# motor_connector_board.net
KiCad netlist of a schematic drawn in EAGLE
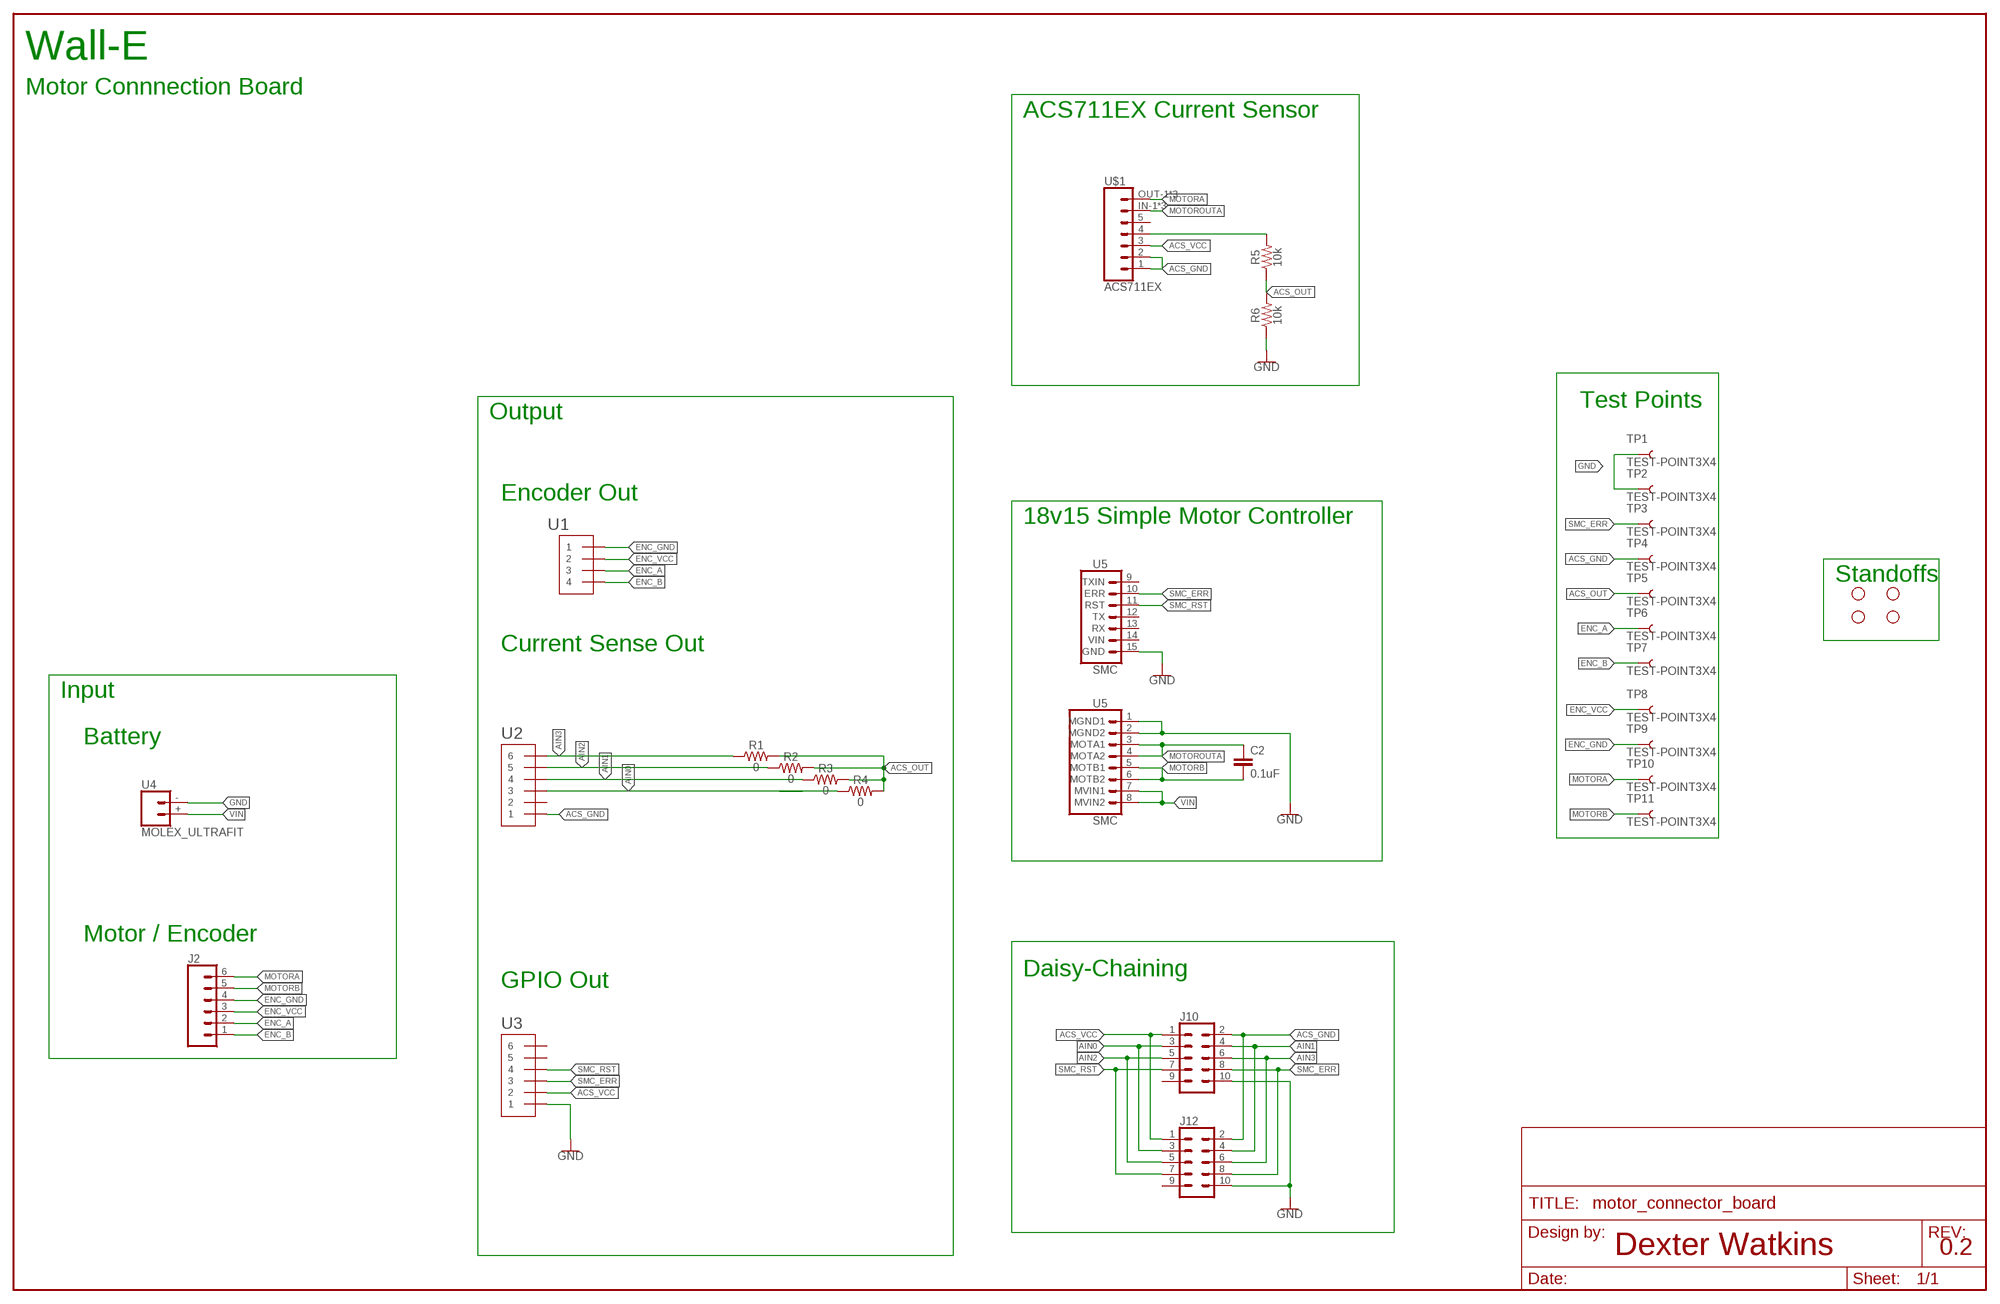
[diagram p0: schematic, sheet 1]

(export (version "E")
  (design (tool "Eeschema 10.0.6"))
  (components
    (comp (ref "C2")
      (value "0.1uF")
      (footprint "eagle-import:0603")
      (libsource (lib "eagle-import") (part "1.0NF/1000PF-0603-50V-10%"))
    )
    (comp (ref "FRAME1")
      (value "FRAME-LEDGER")
      (footprint "eagle-import:CREATIVE_COMMONS")
      (libsource (lib "eagle-import") (part "FRAME-LEDGER"))
    )
    (comp (ref "H1")
      (value "STAND-OFF")
      (footprint "eagle-import:STAND-OFF")
      (libsource (lib "eagle-import") (part "STAND-OFF"))
    )
    (comp (ref "H2")
      (value "STAND-OFF")
      (footprint "eagle-import:STAND-OFF")
      (libsource (lib "eagle-import") (part "STAND-OFF"))
    )
    (comp (ref "H3")
      (value "STAND-OFF")
      (footprint "eagle-import:STAND-OFF")
      (libsource (lib "eagle-import") (part "STAND-OFF"))
    )
    (comp (ref "H4")
      (value "STAND-OFF")
      (footprint "eagle-import:STAND-OFF")
      (libsource (lib "eagle-import") (part "STAND-OFF"))
    )
    (comp (ref "J2")
      (value "CONN_06LONGPADS")
      (footprint "eagle-import:1X06_LONGPADS")
      (libsource (lib "eagle-import") (part "CONN_06LONGPADS"))
    )
    (comp (ref "J10")
      (value "CONN_05X2SHD_LOCK")
      (footprint "eagle-import:2X5-SHROUDED_LOCK")
      (libsource (lib "eagle-import") (part "CONN_05X2SHD_LOCK"))
    )
    (comp (ref "J12")
      (value "CONN_05X2SHD_LOCK")
      (footprint "eagle-import:2X5-SHROUDED_LOCK")
      (libsource (lib "eagle-import") (part "CONN_05X2SHD_LOCK"))
    )
    (comp (ref "R1")
      (value "0")
      (footprint "eagle-import:0603")
      (libsource (lib "eagle-import") (part "0OHM-0603-1/10W-5%"))
    )
    (comp (ref "R2")
      (value "0")
      (footprint "eagle-import:0603")
      (libsource (lib "eagle-import") (part "0OHM-0603-1/10W-5%"))
    )
    (comp (ref "R3")
      (value "0")
      (footprint "eagle-import:0603")
      (libsource (lib "eagle-import") (part "0OHM-0603-1/10W-5%"))
    )
    (comp (ref "R4")
      (value "0")
      (footprint "eagle-import:0603")
      (libsource (lib "eagle-import") (part "0OHM-0603-1/10W-5%"))
    )
    (comp (ref "R5")
      (value "10k")
      (footprint "eagle-import:0603")
      (libsource (lib "eagle-import") (part "10KOHM-0603-1/10W-1%"))
    )
    (comp (ref "R6")
      (value "10k")
      (footprint "eagle-import:0603")
      (libsource (lib "eagle-import") (part "10KOHM-0603-1/10W-1%"))
    )
    (comp (ref "TP1")
      (value "TEST-POINT3X4")
      (footprint "eagle-import:PAD.03X.04")
      (libsource (lib "eagle-import") (part "TEST-POINT3X4"))
    )
    (comp (ref "TP2")
      (value "TEST-POINT3X4")
      (footprint "eagle-import:PAD.03X.04")
      (libsource (lib "eagle-import") (part "TEST-POINT3X4"))
    )
    (comp (ref "TP3")
      (value "TEST-POINT3X4")
      (footprint "eagle-import:PAD.03X.04")
      (libsource (lib "eagle-import") (part "TEST-POINT3X4"))
    )
    (comp (ref "TP4")
      (value "TEST-POINT3X4")
      (footprint "eagle-import:PAD.03X.04")
      (libsource (lib "eagle-import") (part "TEST-POINT3X4"))
    )
    (comp (ref "TP5")
      (value "TEST-POINT3X4")
      (footprint "eagle-import:PAD.03X.04")
      (libsource (lib "eagle-import") (part "TEST-POINT3X4"))
    )
    (comp (ref "TP6")
      (value "TEST-POINT3X4")
      (footprint "eagle-import:PAD.03X.04")
      (libsource (lib "eagle-import") (part "TEST-POINT3X4"))
    )
    (comp (ref "TP7")
      (value "TEST-POINT3X4")
      (footprint "eagle-import:PAD.03X.04")
      (libsource (lib "eagle-import") (part "TEST-POINT3X4"))
    )
    (comp (ref "TP8")
      (value "TEST-POINT3X4")
      (footprint "eagle-import:PAD.03X.04")
      (libsource (lib "eagle-import") (part "TEST-POINT3X4"))
    )
    (comp (ref "TP9")
      (value "TEST-POINT3X4")
      (footprint "eagle-import:PAD.03X.04")
      (libsource (lib "eagle-import") (part "TEST-POINT3X4"))
    )
    (comp (ref "TP10")
      (value "TEST-POINT3X4")
      (footprint "eagle-import:PAD.03X.04")
      (libsource (lib "eagle-import") (part "TEST-POINT3X4"))
    )
    (comp (ref "TP11")
      (value "TEST-POINT3X4")
      (footprint "eagle-import:PAD.03X.04")
      (libsource (lib "eagle-import") (part "TEST-POINT3X4"))
    )
    (comp (ref "U$1")
      (value "ACS711EX")
      (footprint "eagle-import:ACS_CURRENT_SENSOR")
      (libsource (lib "eagle-import") (part "ACS711EX"))
    )
    (comp (ref "U1")
      (value "JST_SH_4")
      (footprint "eagle-import:JST_SH_4_SMD")
      (libsource (lib "eagle-import") (part "JST_SH_4"))
    )
    (comp (ref "U2")
      (value "JST_SH_6")
      (footprint "eagle-import:JST_SH_6")
      (libsource (lib "eagle-import") (part "JST_SH_6"))
    )
    (comp (ref "U3")
      (value "JST_SH_6")
      (footprint "eagle-import:JST_SH_6")
      (libsource (lib "eagle-import") (part "JST_SH_6"))
    )
    (comp (ref "U4")
      (value "MOLEX_ULTRAFIT")
      (footprint "eagle-import:MOLEX_ULTRAFIT-2CKT")
      (libsource (lib "eagle-import") (part "MOLEX_ULTRAFIT"))
    )
    (comp (ref "U5")
      (value "SMC")
      (footprint "eagle-import:SMC")
      (libsource (lib "eagle-import") (part "SMC"))
    )
  )
  (nets
    (net (code "1") (name "ACS_GND") (class "Default")
      (node (ref "J10") (pin "2") (pinfunction "2_2") (pintype "passive"))
      (node (ref "J12") (pin "2") (pinfunction "2_2") (pintype "passive"))
      (node (ref "TP4") (pin "P$1") (pinfunction "1_P$1") (pintype "bidirectional"))
      (node (ref "U$1") (pin "1") (pinfunction "1_1") (pintype "passive"))
      (node (ref "U$1") (pin "2") (pinfunction "2_2") (pintype "passive"))
      (node (ref "U2") (pin "1") (pinfunction "1_1") (pintype "bidirectional"))
    )
    (net (code "2") (name "ACS_OUT") (class "Default")
      (node (ref "R1") (pin "2") (pinfunction "2_2") (pintype "passive"))
      (node (ref "R2") (pin "2") (pinfunction "2_2") (pintype "passive"))
      (node (ref "R3") (pin "2") (pinfunction "2_2") (pintype "passive"))
      (node (ref "R4") (pin "2") (pinfunction "2_2") (pintype "passive"))
      (node (ref "R5") (pin "1") (pinfunction "1_1") (pintype "passive"))
      (node (ref "R6") (pin "2") (pinfunction "2_2") (pintype "passive"))
      (node (ref "TP5") (pin "P$1") (pinfunction "1_P$1") (pintype "bidirectional"))
    )
    (net (code "3") (name "ACS_VCC") (class "Default")
      (node (ref "J10") (pin "1") (pinfunction "1_1") (pintype "passive"))
      (node (ref "J12") (pin "1") (pinfunction "1_1") (pintype "passive"))
      (node (ref "U$1") (pin "3") (pinfunction "3_3") (pintype "passive"))
      (node (ref "U3") (pin "2") (pinfunction "2_2") (pintype "bidirectional"))
    )
    (net (code "4") (name "AIN0") (class "Default")
      (node (ref "J10") (pin "3") (pinfunction "3_3") (pintype "passive"))
      (node (ref "J12") (pin "3") (pinfunction "3_3") (pintype "passive"))
      (node (ref "R4") (pin "1") (pinfunction "1_1") (pintype "passive"))
      (node (ref "U2") (pin "3") (pinfunction "3_3") (pintype "bidirectional"))
    )
    (net (code "5") (name "AIN1") (class "Default")
      (node (ref "J10") (pin "4") (pinfunction "4_4") (pintype "passive"))
      (node (ref "J12") (pin "4") (pinfunction "4_4") (pintype "passive"))
      (node (ref "R3") (pin "1") (pinfunction "1_1") (pintype "passive"))
      (node (ref "U2") (pin "4") (pinfunction "4_4") (pintype "bidirectional"))
    )
    (net (code "6") (name "AIN2") (class "Default")
      (node (ref "J10") (pin "5") (pinfunction "5_5") (pintype "passive"))
      (node (ref "J12") (pin "5") (pinfunction "5_5") (pintype "passive"))
      (node (ref "R2") (pin "1") (pinfunction "1_1") (pintype "passive"))
      (node (ref "U2") (pin "5") (pinfunction "5_5") (pintype "bidirectional"))
    )
    (net (code "7") (name "AIN3") (class "Default")
      (node (ref "J10") (pin "6") (pinfunction "6_6") (pintype "passive"))
      (node (ref "J12") (pin "6") (pinfunction "6_6") (pintype "passive"))
      (node (ref "R1") (pin "1") (pinfunction "1_1") (pintype "passive"))
      (node (ref "U2") (pin "6") (pinfunction "6_6") (pintype "bidirectional"))
    )
    (net (code "8") (name "ENC_A") (class "Default")
      (node (ref "J2") (pin "2") (pinfunction "2_2") (pintype "passive"))
      (node (ref "TP6") (pin "P$1") (pinfunction "1_P$1") (pintype "bidirectional"))
      (node (ref "U1") (pin "3") (pinfunction "3_3") (pintype "bidirectional"))
    )
    (net (code "9") (name "ENC_B") (class "Default")
      (node (ref "J2") (pin "1") (pinfunction "1_1") (pintype "passive"))
      (node (ref "TP7") (pin "P$1") (pinfunction "1_P$1") (pintype "bidirectional"))
      (node (ref "U1") (pin "4") (pinfunction "4_4") (pintype "bidirectional"))
    )
    (net (code "10") (name "ENC_GND") (class "Default")
      (node (ref "J2") (pin "4") (pinfunction "4_4") (pintype "passive"))
      (node (ref "TP9") (pin "P$1") (pinfunction "1_P$1") (pintype "bidirectional"))
      (node (ref "U1") (pin "1") (pinfunction "1_1") (pintype "bidirectional"))
    )
    (net (code "11") (name "ENC_VCC") (class "Default")
      (node (ref "J2") (pin "3") (pinfunction "3_3") (pintype "passive"))
      (node (ref "TP8") (pin "P$1") (pinfunction "1_P$1") (pintype "bidirectional"))
      (node (ref "U1") (pin "2") (pinfunction "2_2") (pintype "bidirectional"))
    )
    (net (code "12") (name "GND") (class "Default")
      (node (ref "J10") (pin "10") (pinfunction "10_10") (pintype "passive"))
      (node (ref "J12") (pin "10") (pinfunction "10_10") (pintype "passive"))
      (node (ref "R6") (pin "1") (pinfunction "1_1") (pintype "passive"))
      (node (ref "TP1") (pin "P$1") (pinfunction "1_P$1") (pintype "bidirectional"))
      (node (ref "TP2") (pin "P$1") (pinfunction "1_P$1") (pintype "bidirectional"))
      (node (ref "U3") (pin "1") (pinfunction "1_1") (pintype "bidirectional"))
      (node (ref "U4") (pin "-") (pinfunction "2_-") (pintype "passive"))
      (node (ref "U5") (pin "1") (pinfunction "MGND1_1") (pintype "passive"))
      (node (ref "U5") (pin "15") (pinfunction "GND_15") (pintype "passive"))
      (node (ref "U5") (pin "2") (pinfunction "MGND2_2") (pintype "passive"))
    )
    (net (code "13") (name "MOTORA") (class "Default")
      (node (ref "J2") (pin "6") (pinfunction "6_6") (pintype "passive"))
      (node (ref "TP10") (pin "P$1") (pinfunction "1_P$1") (pintype "bidirectional"))
      (node (ref "U$1") (pin "OUT-1") (pinfunction "7_OUT-1") (pintype "passive"))
      (node (ref "U$1") (pin "OUT-2") (pinfunction "7_OUT-2") (pintype "passive"))
      (node (ref "U$1") (pin "OUT-3") (pinfunction "7_OUT-3") (pintype "passive"))
    )
    (net (code "14") (name "MOTORB") (class "Default")
      (node (ref "C2") (pin "2") (pinfunction "2_2") (pintype "passive"))
      (node (ref "J2") (pin "5") (pinfunction "5_5") (pintype "passive"))
      (node (ref "TP11") (pin "P$1") (pinfunction "1_P$1") (pintype "bidirectional"))
      (node (ref "U5") (pin "5") (pinfunction "MOTB1_5") (pintype "passive"))
      (node (ref "U5") (pin "6") (pinfunction "MOTB2_6") (pintype "passive"))
    )
    (net (code "15") (name "MOTOROUTA") (class "Default")
      (node (ref "C2") (pin "1") (pinfunction "1_1") (pintype "passive"))
      (node (ref "U$1") (pin "IN-1") (pinfunction "6_IN-1") (pintype "passive"))
      (node (ref "U$1") (pin "IN-2") (pinfunction "6_IN-2") (pintype "passive"))
      (node (ref "U$1") (pin "IN-3") (pinfunction "6_IN-3") (pintype "passive"))
      (node (ref "U5") (pin "3") (pinfunction "MOTA1_3") (pintype "passive"))
      (node (ref "U5") (pin "4") (pinfunction "MOTA2_4") (pintype "passive"))
    )
    (net (code "16") (name "Net-(R5-Pad2)") (class "Default")
      (node (ref "R5") (pin "2") (pinfunction "2_2") (pintype "passive"))
      (node (ref "U$1") (pin "4") (pinfunction "4_4") (pintype "passive"))
    )
    (net (code "17") (name "SMC_ERR") (class "Default")
      (node (ref "J10") (pin "8") (pinfunction "8_8") (pintype "passive"))
      (node (ref "J12") (pin "8") (pinfunction "8_8") (pintype "passive"))
      (node (ref "TP3") (pin "P$1") (pinfunction "1_P$1") (pintype "bidirectional"))
      (node (ref "U3") (pin "3") (pinfunction "3_3") (pintype "bidirectional"))
      (node (ref "U5") (pin "10") (pinfunction "ERR_10") (pintype "passive"))
    )
    (net (code "18") (name "SMC_RST") (class "Default")
      (node (ref "J10") (pin "7") (pinfunction "7_7") (pintype "passive"))
      (node (ref "J12") (pin "7") (pinfunction "7_7") (pintype "passive"))
      (node (ref "U3") (pin "4") (pinfunction "4_4") (pintype "bidirectional"))
      (node (ref "U5") (pin "11") (pinfunction "RST_11") (pintype "passive"))
    )
    (net (code "19") (name "VIN") (class "Default")
      (node (ref "U4") (pin "+") (pinfunction "1_+") (pintype "passive"))
      (node (ref "U5") (pin "7") (pinfunction "MVIN1_7") (pintype "passive"))
      (node (ref "U5") (pin "8") (pinfunction "MVIN2_8") (pintype "passive"))
    )
    (net (code "20") (name "unconnected-(J10-Pad9)") (class "Default")
      (node (ref "J10") (pin "9") (pinfunction "9_9") (pintype "passive"))
    )
    (net (code "21") (name "unconnected-(J12-Pad9)") (class "Default")
      (node (ref "J12") (pin "9") (pinfunction "9_9") (pintype "passive"))
    )
    (net (code "22") (name "unconnected-(U$1-Pad5)") (class "Default")
      (node (ref "U$1") (pin "5") (pinfunction "5_5") (pintype "passive"))
    )
    (net (code "23") (name "unconnected-(U2-Pad2)") (class "Default")
      (node (ref "U2") (pin "2") (pinfunction "2_2") (pintype "bidirectional"))
    )
    (net (code "24") (name "unconnected-(U3-Pad5)") (class "Default")
      (node (ref "U3") (pin "5") (pinfunction "5_5") (pintype "bidirectional"))
    )
    (net (code "25") (name "unconnected-(U3-Pad6)") (class "Default")
      (node (ref "U3") (pin "6") (pinfunction "6_6") (pintype "bidirectional"))
    )
    (net (code "26") (name "unconnected-(U5-RX-Pad13)") (class "Default")
      (node (ref "U5") (pin "13") (pinfunction "RX_13") (pintype "passive"))
    )
    (net (code "27") (name "unconnected-(U5-TX-Pad12)") (class "Default")
      (node (ref "U5") (pin "12") (pinfunction "TX_12") (pintype "passive"))
    )
    (net (code "28") (name "unconnected-(U5-TXIN-Pad9)") (class "Default")
      (node (ref "U5") (pin "9") (pinfunction "TXIN_9") (pintype "passive"))
    )
    (net (code "29") (name "unconnected-(U5-VIN-Pad14)") (class "Default")
      (node (ref "U5") (pin "14") (pinfunction "VIN_14") (pintype "passive"))
    )
  )
)
